# LDOs.net
KiCad netlist of a schematic drawn in Altium Designer
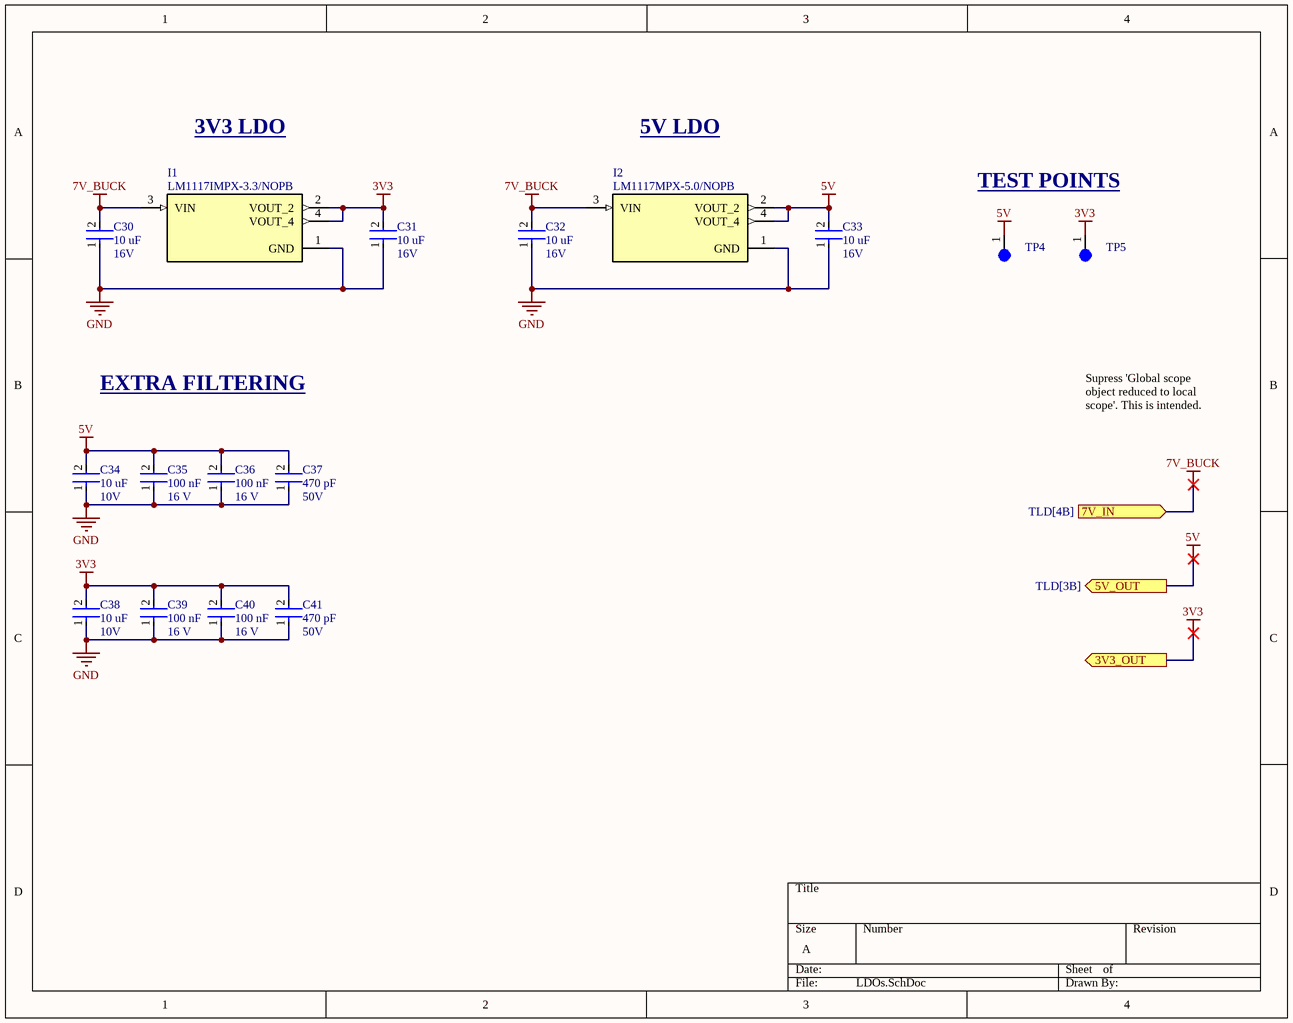
[diagram p0: LDOs.SchDoc]

(export (version "E")
  (design (tool "Eeschema 10.0.6"))
  (components
    (comp (ref "C30")
      (value "293D106X9016A2TE3")
      (footprint "CAP-1210")
      (description "CAP TANT 10UF 10% 16V 1206")
      (fields (field (name "VOLTAGE") "16V") (field (name "CAPACITANCE") "10 uF"))
      (libsource (lib "JLC_25") (part "CAP-10U-0003"))
    )
    (comp (ref "C31")
      (value "293D106X9016A2TE3")
      (footprint "CAP-1210")
      (description "CAP TANT 10UF 10% 16V 1206")
      (fields (field (name "VOLTAGE") "16V") (field (name "CAPACITANCE") "10 uF"))
      (libsource (lib "JLC_25") (part "CAP-10U-0003"))
    )
    (comp (ref "C32")
      (value "293D106X9016A2TE3")
      (footprint "CAP-1210")
      (description "CAP TANT 10UF 10% 16V 1206")
      (fields (field (name "VOLTAGE") "16V") (field (name "CAPACITANCE") "10 uF"))
      (libsource (lib "JLC_25") (part "CAP-10U-0003"))
    )
    (comp (ref "C33")
      (value "293D106X9016A2TE3")
      (footprint "CAP-1210")
      (description "CAP TANT 10UF 10% 16V 1206")
      (fields (field (name "VOLTAGE") "16V") (field (name "CAPACITANCE") "10 uF"))
      (libsource (lib "JLC_25") (part "CAP-10U-0003"))
    )
    (comp (ref "C34")
      (value "CC0603KRX5R6BB106")
      (footprint "CAP-0603")
      (description "CAP CER 10UF 10V X5R 0603")
      (fields (field (name "VOLTAGE") "10V") (field (name "CAPACITANCE") "10 uF"))
      (libsource (lib "JLC_25") (part "CAP-10U-0001"))
    )
    (comp (ref "C35")
      (value "CC0402KRX7R7BB104")
      (footprint "CAP-0402")
      (description "CAP CER 0.1UF 16V X7R 0402")
      (fields (field (name "VOLTAGE RATING") "16 V") (field (name "CAPACITANCE") "100 nF"))
      (libsource (lib "JLC_25") (part "CAP-0.1U-0001"))
    )
    (comp (ref "C36")
      (value "CC0402KRX7R7BB104")
      (footprint "CAP-0402")
      (description "CAP CER 0.1UF 16V X7R 0402")
      (fields (field (name "VOLTAGE RATING") "16 V") (field (name "CAPACITANCE") "100 nF"))
      (libsource (lib "JLC_25") (part "CAP-0.1U-0001"))
    )
    (comp (ref "C37")
      (value "CC0805JRNPO9BN471")
      (footprint "CAP-0805")
      (description "CAP CER 470PF 50V C0G/NPO 0805")
      (fields (field (name "VOLTAGE") "50V") (field (name "CAPACITANCE") "470 pF"))
      (libsource (lib "JLC_25") (part "CAP-470P-0001"))
    )
    (comp (ref "C38")
      (value "CC0603KRX5R6BB106")
      (footprint "CAP-0603")
      (description "CAP CER 10UF 10V X5R 0603")
      (fields (field (name "VOLTAGE") "10V") (field (name "CAPACITANCE") "10 uF"))
      (libsource (lib "JLC_25") (part "CAP-10U-0001"))
    )
    (comp (ref "C39")
      (value "CC0402KRX7R7BB104")
      (footprint "CAP-0402")
      (description "CAP CER 0.1UF 16V X7R 0402")
      (fields (field (name "VOLTAGE RATING") "16 V") (field (name "CAPACITANCE") "100 nF"))
      (libsource (lib "JLC_25") (part "CAP-0.1U-0001"))
    )
    (comp (ref "C40")
      (value "CC0402KRX7R7BB104")
      (footprint "CAP-0402")
      (description "CAP CER 0.1UF 16V X7R 0402")
      (fields (field (name "VOLTAGE RATING") "16 V") (field (name "CAPACITANCE") "100 nF"))
      (libsource (lib "JLC_25") (part "CAP-0.1U-0001"))
    )
    (comp (ref "C41")
      (value "CC0805JRNPO9BN471")
      (footprint "CAP-0805")
      (description "CAP CER 470PF 50V C0G/NPO 0805")
      (fields (field (name "VOLTAGE") "50V") (field (name "CAPACITANCE") "470 pF"))
      (libsource (lib "JLC_25") (part "CAP-470P-0001"))
    )
    (comp (ref "I1")
      (value "LM1117IMPX-3.3/NOPB")
      (footprint "IC-SOT-223-4")
      (description "IC REG LIN 3.3V 800MA SOT223-4")
      (libsource (lib "JLC_25") (part "IC_LDO_3V3_0001"))
    )
    (comp (ref "I2")
      (value "LM1117MPX-5.0/NOPB")
      (footprint "IC-SOT-223-4")
      (description "IC REG LINEAR 5V 800MA SOT223-4")
      (libsource (lib "JLC_25") (part "IC_LDO_5V_0001"))
    )
    (comp (ref "TP4")
      (value "5003")
      (footprint "TEST-POINT-0001")
      (description "Oranange PC Test Point, Miniature Phoisphor Bronze Silver Plating Through Hole Mounting Type")
      (libsource (lib "*") (part "TEST-POINT-0001"))
    )
    (comp (ref "TP5")
      (value "5003")
      (footprint "TEST-POINT-0001")
      (description "Oranange PC Test Point, Miniature Phoisphor Bronze Silver Plating Through Hole Mounting Type")
      (libsource (lib "*") (part "TEST-POINT-0001"))
    )
  )
  (nets
    (net (code "1") (name "3V3") (class "Default")
      (node (ref "C31") (pin "2") (pinfunction "2_2") (pintype "passive"))
      (node (ref "C38") (pin "2") (pinfunction "2_2") (pintype "passive"))
      (node (ref "C39") (pin "2") (pinfunction "2_2") (pintype "passive"))
      (node (ref "C40") (pin "2") (pinfunction "2_2") (pintype "passive"))
      (node (ref "C41") (pin "2") (pinfunction "2_2") (pintype "passive"))
      (node (ref "I1") (pin "2") (pinfunction "VOUT_2_2") (pintype "output"))
      (node (ref "I1") (pin "4") (pinfunction "VOUT_4_4") (pintype "output"))
      (node (ref "TP5") (pin "1") (pinfunction "0_1") (pintype "passive"))
    )
    (net (code "2") (name "5V") (class "Default")
      (node (ref "C33") (pin "2") (pinfunction "2_2") (pintype "passive"))
      (node (ref "C34") (pin "2") (pinfunction "2_2") (pintype "passive"))
      (node (ref "C35") (pin "2") (pinfunction "2_2") (pintype "passive"))
      (node (ref "C36") (pin "2") (pinfunction "2_2") (pintype "passive"))
      (node (ref "C37") (pin "2") (pinfunction "2_2") (pintype "passive"))
      (node (ref "I2") (pin "2") (pinfunction "VOUT_2_2") (pintype "output"))
      (node (ref "I2") (pin "4") (pinfunction "VOUT_4_4") (pintype "output"))
      (node (ref "TP4") (pin "1") (pinfunction "0_1") (pintype "passive"))
    )
    (net (code "3") (name "7V_BUCK") (class "Default")
      (node (ref "C30") (pin "2") (pinfunction "2_2") (pintype "passive"))
      (node (ref "C32") (pin "2") (pinfunction "2_2") (pintype "passive"))
      (node (ref "I1") (pin "3") (pinfunction "VIN_3") (pintype "input"))
      (node (ref "I2") (pin "3") (pinfunction "VIN_3") (pintype "input"))
    )
    (net (code "4") (name "GND") (class "Default")
      (node (ref "C30") (pin "1") (pinfunction "1_1") (pintype "passive"))
      (node (ref "C31") (pin "1") (pinfunction "1_1") (pintype "passive"))
      (node (ref "C32") (pin "1") (pinfunction "1_1") (pintype "passive"))
      (node (ref "C33") (pin "1") (pinfunction "1_1") (pintype "passive"))
      (node (ref "C34") (pin "1") (pinfunction "1_1") (pintype "passive"))
      (node (ref "C35") (pin "1") (pinfunction "1_1") (pintype "passive"))
      (node (ref "C36") (pin "1") (pinfunction "1_1") (pintype "passive"))
      (node (ref "C37") (pin "1") (pinfunction "1_1") (pintype "passive"))
      (node (ref "C38") (pin "1") (pinfunction "1_1") (pintype "passive"))
      (node (ref "C39") (pin "1") (pinfunction "1_1") (pintype "passive"))
      (node (ref "C40") (pin "1") (pinfunction "1_1") (pintype "passive"))
      (node (ref "C41") (pin "1") (pinfunction "1_1") (pintype "passive"))
      (node (ref "I1") (pin "1") (pinfunction "GND_1") (pintype "power_in"))
      (node (ref "I2") (pin "1") (pinfunction "GND_1") (pintype "power_in"))
    )
  )
)
